# classwork_2_0.net
KiCad netlist of a schematic drawn in Altium Designer
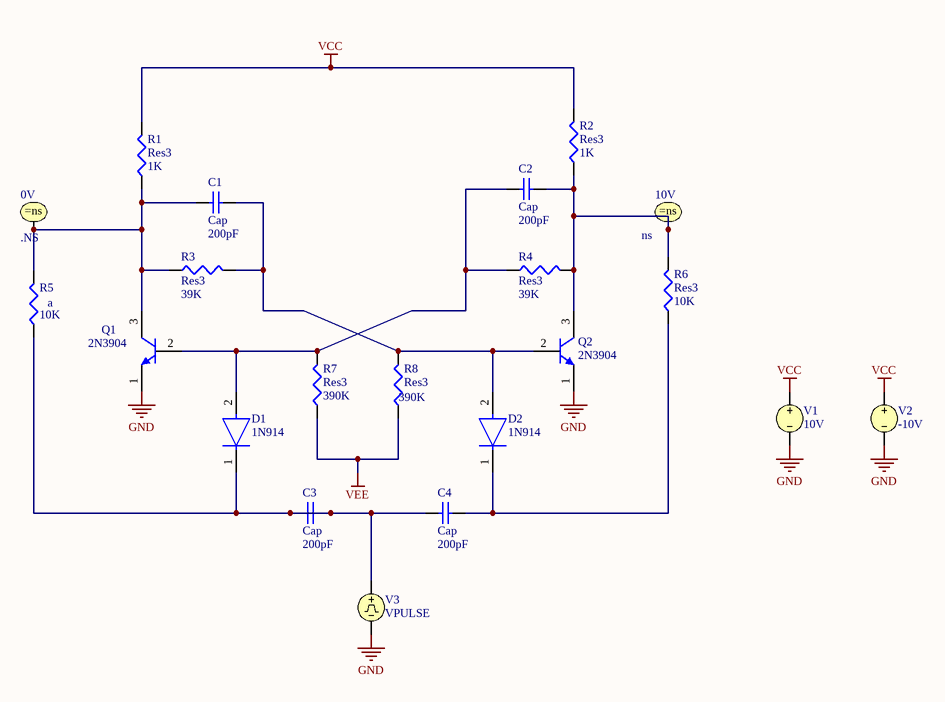
[diagram p0: classwork 2.0.SchDoc]

(export (version "E")
  (design (tool "Eeschema 10.0.6"))
  (components
    (comp (ref "0V")
      (value ".NS")
      (description "Node Set")
      (fields (field (name "PUBLISHER") "Altium Limited"))
      (libsource (lib "Simulation Sources (2)") (part ".NS"))
    )
    (comp (ref "10V")
      (value "ns")
      (description "Node Set")
      (fields (field (name "PUBLISHER") "Altium Limited"))
      (libsource (lib "Simulation Sources (1)") (part ".NS"))
    )
    (comp (ref "C1")
      (value "Cap")
      (footprint "RAD-0.3")
      (description "Capacitor")
      (fields (field (name "ALTIUM_VALUE") "200pF") (field (name "PUBLISHER") "Altium Limited"))
      (libsource (lib "Miscellaneous Devices") (part "Cap"))
    )
    (comp (ref "C2")
      (value "Cap")
      (footprint "RAD-0.3")
      (description "Capacitor")
      (fields (field (name "ALTIUM_VALUE") "200pF") (field (name "PUBLISHER") "Altium Limited"))
      (libsource (lib "Miscellaneous Devices") (part "Cap"))
    )
    (comp (ref "C3")
      (value "Cap")
      (footprint "RAD-0.3")
      (description "Capacitor")
      (fields (field (name "ALTIUM_VALUE") "200pF") (field (name "PUBLISHER") "Altium Limited"))
      (libsource (lib "Miscellaneous Devices") (part "Cap"))
    )
    (comp (ref "C4")
      (value "Cap")
      (footprint "RAD-0.3")
      (description "Capacitor")
      (fields (field (name "ALTIUM_VALUE") "200pF") (field (name "PUBLISHER") "Altium Limited"))
      (libsource (lib "Miscellaneous Devices") (part "Cap"))
    )
    (comp (ref "D1")
      (value "1N914")
      (footprint "FP-502-01-MFG")
      (description "DIODE GEN PURP 75V 200MA SOD523F")
      (fields
        (field (name "MANUFACTURER PART NUMBER") "1N914BWT")
        (field (name "OCTOPART") "https://octopart.com/1n914bwt-on+semiconductor-84323166")
      )
      (libsource (lib "Altium Content Vault") (part "d7152d700b627762746794eb795d46e"))
    )
    (comp (ref "D2")
      (value "1N914")
      (footprint "FP-502-01-MFG")
      (description "DIODE GEN PURP 75V 200MA SOD523F")
      (fields
        (field (name "MANUFACTURER PART NUMBER") "1N914BWT")
        (field (name "OCTOPART") "https://octopart.com/1n914bwt-on+semiconductor-84323166")
      )
      (libsource (lib "Altium Content Vault") (part "d7152d700b627762746794eb795d46e"))
    )
    (comp (ref "Q1")
      (value "2N3904")
      (footprint "ONSC-TO-92-3-29-11")
      (description "General Purpose Transistor, NPN Silicon, 200 mA, 60 V, -55 to 150 degC, 3-Pin TO-92, RoHS, Bulk")
      (fields (field (name "MANUFACTURER") "ONSemiconductor"))
      (libsource (lib "BJT") (part "CMP-2000-05562-1"))
    )
    (comp (ref "Q2")
      (value "2N3904")
      (footprint "ONSC-TO-92-3-29-11")
      (description "General Purpose Transistor, NPN Silicon, 200 mA, 60 V, -55 to 150 degC, 3-Pin TO-92, RoHS, Bulk")
      (fields (field (name "MANUFACTURER") "ONSemiconductor"))
      (libsource (lib "BJT") (part "CMP-2000-05562-1"))
    )
    (comp (ref "R1")
      (value "Res3")
      (footprint "J1-0603")
      (description "Resistor")
      (fields (field (name "ALTIUM_VALUE") "1K") (field (name "PUBLISHER") "Altium Limited"))
      (libsource (lib "Miscellaneous Devices") (part "Res3"))
    )
    (comp (ref "R2")
      (value "Res3")
      (footprint "J1-0603")
      (description "Resistor")
      (fields (field (name "ALTIUM_VALUE") "1K") (field (name "PUBLISHER") "Altium Limited"))
      (libsource (lib "Miscellaneous Devices") (part "Res3"))
    )
    (comp (ref "R3")
      (value "Res3")
      (footprint "J1-0603")
      (description "Resistor")
      (fields (field (name "ALTIUM_VALUE") "39K") (field (name "PUBLISHER") "Altium Limited"))
      (libsource (lib "Miscellaneous Devices") (part "Res3"))
    )
    (comp (ref "R4")
      (value "Res3")
      (footprint "J1-0603")
      (description "Resistor")
      (fields (field (name "ALTIUM_VALUE") "39K") (field (name "PUBLISHER") "Altium Limited"))
      (libsource (lib "Miscellaneous Devices") (part "Res3"))
    )
    (comp (ref "R5")
      (value "a")
      (footprint "J1-0603")
      (description "Resistor")
      (fields (field (name "ALTIUM_VALUE") "10K") (field (name "PUBLISHER") "Altium Limited"))
      (libsource (lib "Miscellaneous Devices") (part "Res3"))
    )
    (comp (ref "R6")
      (value "Res3")
      (footprint "J1-0603")
      (description "Resistor")
      (fields (field (name "ALTIUM_VALUE") "10K") (field (name "PUBLISHER") "Altium Limited"))
      (libsource (lib "Miscellaneous Devices") (part "Res3"))
    )
    (comp (ref "R7")
      (value "Res3")
      (footprint "J1-0603")
      (description "Resistor")
      (fields (field (name "ALTIUM_VALUE") "390K") (field (name "PUBLISHER") "Altium Limited"))
      (libsource (lib "Miscellaneous Devices") (part "Res3"))
    )
    (comp (ref "R8")
      (value "Res3")
      (footprint "J1-0603")
      (description "Resistor")
      (fields (field (name "ALTIUM_VALUE") "390K") (field (name "PUBLISHER") "Altium Limited"))
      (libsource (lib "Miscellaneous Devices") (part "Res3"))
    )
    (comp (ref "V1")
      (value "10V")
      (description "Voltage Source")
      (fields (field (name "PUBLISHER") "Altium Limited"))
      (libsource (lib "Simulation Sources (1)") (part "VSRC"))
    )
    (comp (ref "V2")
      (value "-10V")
      (description "Voltage Source")
      (fields (field (name "PUBLISHER") "Altium Limited"))
      (libsource (lib "Simulation Sources (1)") (part "VSRC"))
    )
    (comp (ref "V3")
      (value "VPULSE")
      (description "Pulse Voltage Source")
      (fields (field (name "PUBLISHER") "Altium Limited"))
      (libsource (lib "Simulation Sources (2)") (part "VPULSE"))
    )
  )
  (nets
    (net (code "1") (name "GND") (class "Default")
      (node (ref "Q1") (pin "1") (pinfunction "E_1") (pintype "passive"))
      (node (ref "Q2") (pin "1") (pinfunction "E_1") (pintype "passive"))
      (node (ref "V1") (pin "2") (pinfunction "2_2") (pintype "passive"))
      (node (ref "V2") (pin "2") (pinfunction "2_2") (pintype "passive"))
      (node (ref "V3") (pin "2") (pinfunction "2_2") (pintype "passive"))
    )
    (net (code "2") (name "Net-(D1-A)") (class "Default")
      (node (ref "C2") (pin "1") (pinfunction "1_1") (pintype "passive"))
      (node (ref "D1") (pin "2") (pinfunction "A_2") (pintype "passive"))
      (node (ref "Q1") (pin "2") (pinfunction "B_2") (pintype "passive"))
      (node (ref "R4") (pin "1") (pinfunction "1_1") (pintype "passive"))
      (node (ref "R7") (pin "2") (pinfunction "2_2") (pintype "passive"))
    )
    (net (code "3") (name "Net-(D1-C)") (class "Default")
      (node (ref "C3") (pin "1") (pinfunction "1_1") (pintype "passive"))
      (node (ref "C3") (pin "2") (pinfunction "2_2") (pintype "passive"))
      (node (ref "C4") (pin "1") (pinfunction "1_1") (pintype "passive"))
      (node (ref "D1") (pin "1") (pinfunction "C_1") (pintype "passive"))
      (node (ref "R5") (pin "1") (pinfunction "1_1") (pintype "passive"))
      (node (ref "V3") (pin "1") (pinfunction "1_1") (pintype "passive"))
    )
    (net (code "4") (name "Net-(D2-A)") (class "Default")
      (node (ref "C1") (pin "2") (pinfunction "2_2") (pintype "passive"))
      (node (ref "D2") (pin "2") (pinfunction "A_2") (pintype "passive"))
      (node (ref "Q2") (pin "2") (pinfunction "B_2") (pintype "passive"))
      (node (ref "R3") (pin "2") (pinfunction "2_2") (pintype "passive"))
      (node (ref "R8") (pin "2") (pinfunction "2_2") (pintype "passive"))
    )
    (net (code "5") (name "Net-(D2-C)") (class "Default")
      (node (ref "C4") (pin "2") (pinfunction "2_2") (pintype "passive"))
      (node (ref "D2") (pin "1") (pinfunction "C_1") (pintype "passive"))
      (node (ref "R6") (pin "1") (pinfunction "1_1") (pintype "passive"))
    )
    (net (code "6") (name "Net-(Q1-C)") (class "Default")
      (node (ref "0V") (pin "1") (pinfunction "1_1") (pintype "passive"))
      (node (ref "C1") (pin "1") (pinfunction "1_1") (pintype "passive"))
      (node (ref "Q1") (pin "3") (pinfunction "C_3") (pintype "passive"))
      (node (ref "R1") (pin "1") (pinfunction "1_1") (pintype "passive"))
      (node (ref "R3") (pin "1") (pinfunction "1_1") (pintype "passive"))
      (node (ref "R5") (pin "2") (pinfunction "2_2") (pintype "passive"))
    )
    (net (code "7") (name "Net-(Q2-C)") (class "Default")
      (node (ref "10V") (pin "1") (pinfunction "1_1") (pintype "passive"))
      (node (ref "C2") (pin "2") (pinfunction "2_2") (pintype "passive"))
      (node (ref "Q2") (pin "3") (pinfunction "C_3") (pintype "passive"))
      (node (ref "R2") (pin "1") (pinfunction "1_1") (pintype "passive"))
      (node (ref "R4") (pin "2") (pinfunction "2_2") (pintype "passive"))
      (node (ref "R6") (pin "2") (pinfunction "2_2") (pintype "passive"))
    )
    (net (code "8") (name "VCC") (class "Default")
      (node (ref "R1") (pin "2") (pinfunction "2_2") (pintype "passive"))
      (node (ref "R2") (pin "2") (pinfunction "2_2") (pintype "passive"))
      (node (ref "V1") (pin "1") (pinfunction "1_1") (pintype "passive"))
      (node (ref "V2") (pin "1") (pinfunction "1_1") (pintype "passive"))
    )
    (net (code "9") (name "VEE") (class "Default")
      (node (ref "R7") (pin "1") (pinfunction "1_1") (pintype "passive"))
      (node (ref "R8") (pin "1") (pinfunction "1_1") (pintype "passive"))
    )
  )
)
